# Mako_DSP_Power_R1_3.net
KiCad netlist of a schematic drawn in Altium Designer
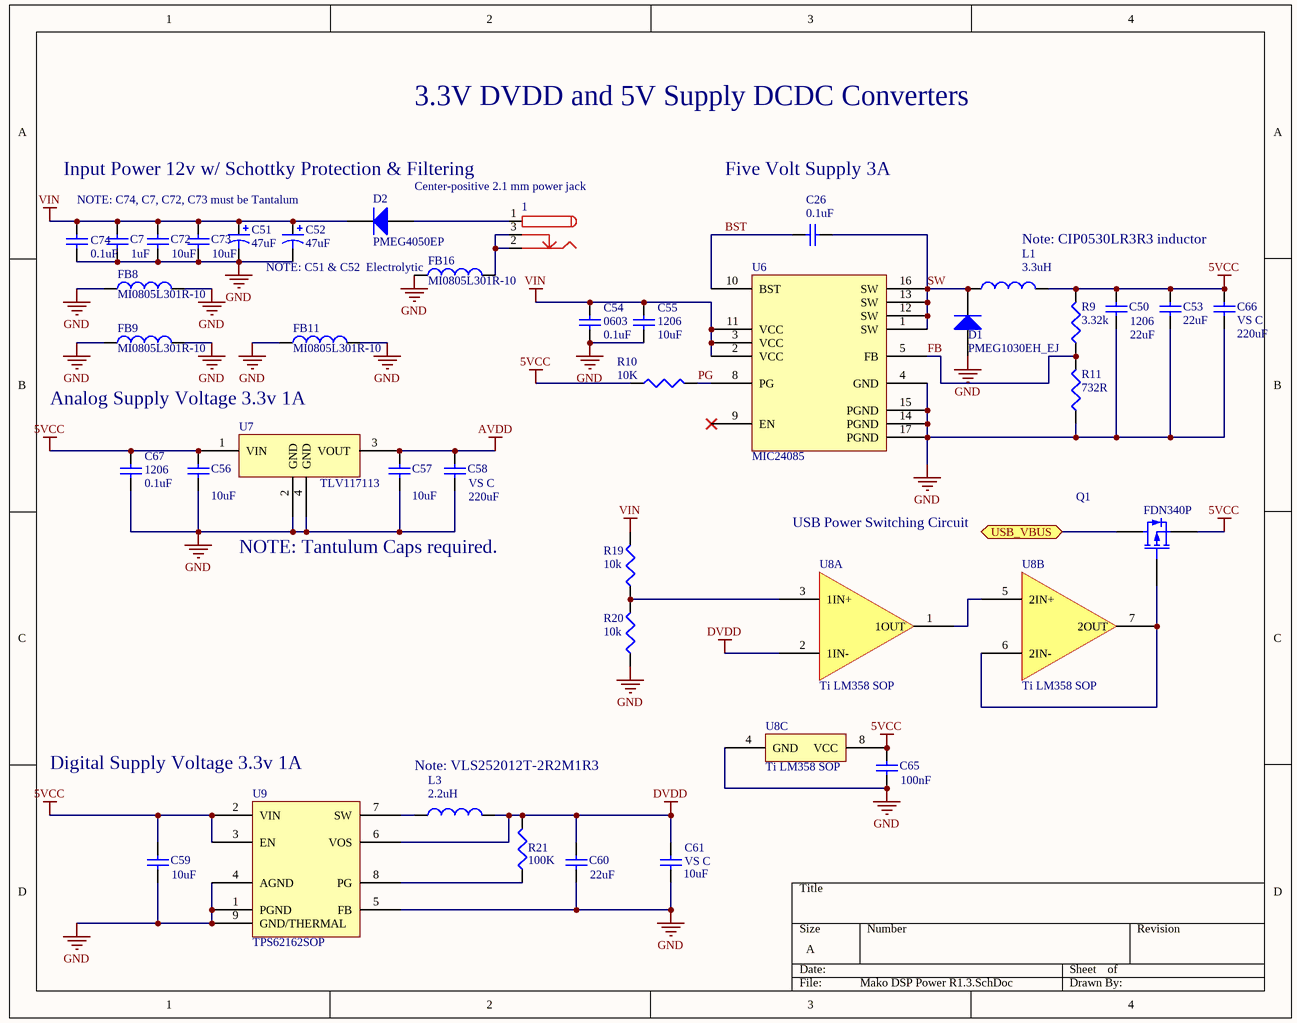
[diagram p0: Mako DSP Power R1.3.SchDoc]

(export (version "E")
  (design (tool "Eeschema 10.0.6"))
  (components
    (comp (ref "1")
      (value "Center-positive 2.1 mm power jack")
      (footprint "PJ-102AH")
      (description "Power jack")
      (fields (field (name "PUBLISHER") "Altium Limited"))
      (libsource (lib "Rascal") (part "PWR2.5"))
    )
    (comp (ref "C7")
      (value "1uF")
      (footprint "C1206")
      (description "Capacitor (Semiconductor SIM Model)")
      (fields (field (name "Comment") "Cap Semi") (field (name "PUBLISHER") "Altium Limited"))
      (libsource (lib "Miscellaneous Devices") (part "Cap Semi"))
    )
    (comp (ref "C26")
      (value "0.1uF")
      (footprint "1608[0603]")
      (description "Capacitor (Semiconductor SIM Model)")
      (fields (field (name "Comment") "Cap Semi") (field (name "PUBLISHER") "Altium Limited"))
      (libsource (lib "Miscellaneous Devices") (part "Cap Semi"))
    )
    (comp (ref "C50")
      (value "1206")
      (footprint "C1206")
      (description "Capacitor (Semiconductor SIM Model)")
      (fields (field (name "ALTIUM_VALUE") "22uF") (field (name "PUBLISHER") "Altium Limited"))
      (libsource (lib "Miscellaneous Devices") (part "Cap Semi"))
    )
    (comp (ref "C51")
      (value "47uF")
      (footprint "CAPPR2.5-6.3x5")
      (description "Polarized Capacitor (Radial)")
      (fields (field (name "Comment") "Cap Pol1") (field (name "PUBLISHER") "Altium Limited"))
      (libsource (lib "Miscellaneous Devices") (part "Cap Pol1"))
    )
    (comp (ref "C52")
      (value "47uF")
      (footprint "CAPPR2.5-6.3x5")
      (description "Polarized Capacitor (Radial)")
      (fields (field (name "Comment") "Cap Pol1") (field (name "PUBLISHER") "Altium Limited"))
      (libsource (lib "Miscellaneous Devices") (part "Cap Pol1"))
    )
    (comp (ref "C53")
      (value "22uF")
      (footprint "C1206")
      (description "Capacitor (Semiconductor SIM Model)")
      (fields (field (name "Comment") "Cap Semi") (field (name "PUBLISHER") "Altium Limited"))
      (libsource (lib "Miscellaneous Devices") (part "Cap Semi"))
    )
    (comp (ref "C54")
      (value "0603")
      (footprint "1608[0603]")
      (description "Capacitor (Semiconductor SIM Model)")
      (fields (field (name "ALTIUM_VALUE") "0.1uF") (field (name "PUBLISHER") "Altium Limited"))
      (libsource (lib "Miscellaneous Devices") (part "Cap Semi"))
    )
    (comp (ref "C55")
      (value "1206")
      (footprint "C1206")
      (description "Capacitor (Semiconductor SIM Model)")
      (fields (field (name "ALTIUM_VALUE") "10uF") (field (name "PUBLISHER") "Altium Limited"))
      (libsource (lib "Miscellaneous Devices") (part "Cap Semi"))
    )
    (comp (ref "C56")
      (value "10uF")
      (footprint "C1206")
      (description "Capacitor (Semiconductor SIM Model)")
      (fields (field (name "Comment") "Cap Semi") (field (name "PUBLISHER") "Altium Limited"))
      (libsource (lib "Miscellaneous Devices") (part "Cap Semi"))
    )
    (comp (ref "C57")
      (value "10uF")
      (footprint "C1206")
      (description "Capacitor (Semiconductor SIM Model)")
      (fields (field (name "Comment") "Cap Semi") (field (name "PUBLISHER") "Altium Limited"))
      (libsource (lib "Miscellaneous Devices") (part "Cap Semi"))
    )
    (comp (ref "C58")
      (value "VS C")
      (footprint "Panasonic VS C")
      (description "Capacitor (Semiconductor SIM Model)")
      (fields (field (name "ALTIUM_VALUE") "220uF") (field (name "PUBLISHER") "Altium Limited"))
      (libsource (lib "Miscellaneous Devices") (part "Cap Semi"))
    )
    (comp (ref "C59")
      (value "10uF")
      (footprint "C1206")
      (description "Capacitor (Semiconductor SIM Model)")
      (fields (field (name "Comment") "Cap Semi") (field (name "PUBLISHER") "Altium Limited"))
      (libsource (lib "Miscellaneous Devices") (part "Cap Semi"))
    )
    (comp (ref "C60")
      (value "22uF")
      (footprint "C1206")
      (description "Capacitor (Semiconductor SIM Model)")
      (fields (field (name "Comment") "Cap Semi") (field (name "PUBLISHER") "Altium Limited"))
      (libsource (lib "Miscellaneous Devices") (part "Cap Semi"))
    )
    (comp (ref "C61")
      (value "VS C")
      (footprint "Panasonic VS C")
      (description "Capacitor (Semiconductor SIM Model)")
      (fields (field (name "ALTIUM_VALUE") "10uF") (field (name "PUBLISHER") "Altium Limited"))
      (libsource (lib "Miscellaneous Devices") (part "Cap Semi"))
    )
    (comp (ref "C65")
      (value "100nF")
      (footprint "1608[0603]")
      (description "Capacitor (Semiconductor SIM Model)")
      (fields (field (name "Comment") "Cap Semi") (field (name "PUBLISHER") "Altium Limited"))
      (libsource (lib "Miscellaneous Devices") (part "Cap Semi"))
    )
    (comp (ref "C66")
      (value "VS C")
      (footprint "Panasonic VS C")
      (description "Capacitor (Semiconductor SIM Model)")
      (fields (field (name "ALTIUM_VALUE") "220uF") (field (name "PUBLISHER") "Altium Limited"))
      (libsource (lib "Miscellaneous Devices") (part "Cap Semi"))
    )
    (comp (ref "C67")
      (value "1206")
      (footprint "C1206")
      (description "Capacitor (Semiconductor SIM Model)")
      (fields (field (name "ALTIUM_VALUE") "0.1uF") (field (name "PUBLISHER") "Altium Limited"))
      (libsource (lib "Miscellaneous Devices") (part "Cap Semi"))
    )
    (comp (ref "C72")
      (value "10uF")
      (footprint "C1206")
      (description "Capacitor (Semiconductor SIM Model)")
      (fields (field (name "Comment") "Cap Semi") (field (name "PUBLISHER") "Altium Limited"))
      (libsource (lib "Miscellaneous Devices") (part "Cap Semi"))
    )
    (comp (ref "C73")
      (value "10uF")
      (footprint "C1206")
      (description "Capacitor (Semiconductor SIM Model)")
      (fields (field (name "Comment") "Cap Semi") (field (name "PUBLISHER") "Altium Limited"))
      (libsource (lib "Miscellaneous Devices") (part "Cap Semi"))
    )
    (comp (ref "C74")
      (value "0.1uF")
      (footprint "C1206")
      (description "Capacitor (Semiconductor SIM Model)")
      (fields (field (name "Comment") "Cap Semi") (field (name "PUBLISHER") "Altium Limited"))
      (libsource (lib "Miscellaneous Devices") (part "Cap Semi"))
    )
    (comp (ref "D1")
      (value "PMEG1030EH_EJ")
      (footprint "PMEG1030EH_EJ")
      (description "Default Diode")
      (fields (field (name "PUBLISHER") "Altium Limited"))
      (libsource (lib "") (part "Diode_1"))
    )
    (comp (ref "D2")
      (value "PMEG4050EP")
      (footprint "PMEG4050EP")
      (description "Default Diode")
      (fields (field (name "PUBLISHER") "Altium Limited"))
      (libsource (lib "Miscellaneous Devices") (part "Diode"))
    )
    (comp (ref "FB8")
      (value "MI0805L301R-10")
      (footprint "SM 0805 - gap trimmed")
      (description "Inductor")
      (fields (field (name "PUBLISHER") "Altium Limited"))
      (libsource (lib "Miscellaneous Devices") (part "Inductor"))
    )
    (comp (ref "FB9")
      (value "MI0805L301R-10")
      (footprint "SM 0805 - gap trimmed")
      (description "Inductor")
      (fields (field (name "PUBLISHER") "Altium Limited"))
      (libsource (lib "Miscellaneous Devices") (part "Inductor"))
    )
    (comp (ref "FB11")
      (value "MI0805L301R-10")
      (footprint "SM 0805 - gap trimmed")
      (description "Inductor")
      (fields (field (name "PUBLISHER") "Altium Limited"))
      (libsource (lib "Miscellaneous Devices") (part "Inductor"))
    )
    (comp (ref "FB16")
      (value "MI0805L301R-10")
      (footprint "SM 0805 - gap trimmed")
      (description "Inductor")
      (fields (field (name "PUBLISHER") "Altium Limited"))
      (libsource (lib "Miscellaneous Devices") (part "Inductor"))
    )
    (comp (ref "L1")
      (value "3.3uH")
      (footprint "CIP0530LR3R3")
      (description "Inductor")
      (fields (field (name "PUBLISHER") "Altium Limited"))
      (libsource (lib "Miscellaneous Devices") (part "Inductor"))
    )
    (comp (ref "L3")
      (value "2.2uH")
      (footprint "VLS252012T-2R2M1R3")
      (description "Inductor")
      (fields (field (name "PUBLISHER") "Altium Limited"))
      (libsource (lib "Miscellaneous Devices") (part "Inductor"))
    )
    (comp (ref "Q1")
      (value "FDN340P")
      (footprint "SOT23-3N")
      (description "P-Channel MOSFET")
      (fields (field (name "PUBLISHER") "Altium Limited"))
      (libsource (lib "Mako DSP Schematic Library") (part "FDN340P"))
    )
    (comp (ref "R9")
      (value "3.32k")
      (footprint "J1-0603")
      (description "Resistor")
      (fields (field (name "Comment") "Res3") (field (name "PUBLISHER") "Altium Limited"))
      (libsource (lib "Miscellaneous Devices") (part "Res3"))
    )
    (comp (ref "R10")
      (value "10K")
      (footprint "J1-0603")
      (description "Resistor")
      (fields (field (name "Comment") "Res3") (field (name "PUBLISHER") "Altium Limited"))
      (libsource (lib "Miscellaneous Devices") (part "Res3"))
    )
    (comp (ref "R11")
      (value "732R")
      (footprint "J1-0603")
      (description "Resistor")
      (fields (field (name "Comment") "Res3") (field (name "PUBLISHER") "Altium Limited"))
      (libsource (lib "Miscellaneous Devices") (part "Res3"))
    )
    (comp (ref "R19")
      (value "10k")
      (footprint "J1-0603")
      (description "Resistor")
      (fields (field (name "Comment") "Res3") (field (name "PUBLISHER") "Altium Limited"))
      (libsource (lib "Miscellaneous Devices") (part "Res3"))
    )
    (comp (ref "R20")
      (value "10k")
      (footprint "J1-0603")
      (description "Resistor")
      (fields (field (name "Comment") "Res3") (field (name "PUBLISHER") "Altium Limited"))
      (libsource (lib "Miscellaneous Devices") (part "Res3"))
    )
    (comp (ref "R21")
      (value "100K")
      (footprint "RESC2012L")
      (description "Resistor")
      (fields (field (name "Comment") "Res3") (field (name "PUBLISHER") "Altium Limited"))
      (libsource (lib "Miscellaneous Devices") (part "Res3"))
    )
    (comp (ref "U6")
      (value "MIC24085")
      (footprint "MIC24085-AYML")
      (libsource (lib "Adams Altium Library") (part "MIC24085"))
    )
    (comp (ref "U7")
      (value "TLV117113")
      (footprint "TLV117112")
      (description "Linear Regulator")
      (libsource (lib "Adams Altium Library") (part "TLV117112"))
    )
    (comp (ref "U8")
      (value "Ti LM358 SOP")
      (footprint "LM358")
      (libsource (lib "Mako DSP Schematic Library") (part "LM358_Symbol"))
    )
    (comp (ref "U9")
      (value "TPS62162SOP")
      (footprint "TPS62162SOP")
      (libsource (lib "Adams Altium Library") (part "TPS62162SOP"))
    )
  )
  (nets
    (net (code "1") (name "/BST") (class "Default")
      (node (ref "C26") (pin "2") (pinfunction "2_2") (pintype "passive"))
      (node (ref "U6") (pin "10") (pinfunction "BST_10") (pintype "passive"))
    )
    (net (code "2") (name "/FB") (class "Default")
      (node (ref "R11") (pin "2") (pinfunction "2_2") (pintype "passive"))
      (node (ref "R9") (pin "1") (pinfunction "1_1") (pintype "passive"))
      (node (ref "U6") (pin "5") (pinfunction "FB_5") (pintype "passive"))
    )
    (net (code "3") (name "/PG") (class "Default")
      (node (ref "R10") (pin "2") (pinfunction "2_2") (pintype "passive"))
      (node (ref "U6") (pin "8") (pinfunction "PG_8") (pintype "passive"))
    )
    (net (code "4") (name "/SW") (class "Default")
      (node (ref "C26") (pin "1") (pinfunction "1_1") (pintype "passive"))
      (node (ref "D1") (pin "2") (pinfunction "K_2") (pintype "passive"))
      (node (ref "L1") (pin "1") (pinfunction "1_1") (pintype "passive"))
      (node (ref "U6") (pin "1") (pinfunction "SW_1") (pintype "passive"))
      (node (ref "U6") (pin "12") (pinfunction "SW_12") (pintype "passive"))
      (node (ref "U6") (pin "13") (pinfunction "SW_13") (pintype "passive"))
      (node (ref "U6") (pin "16") (pinfunction "SW_16") (pintype "passive"))
    )
    (net (code "5") (name "/USB_VBUS") (class "Default")
      (node (ref "Q1") (pin "3") (pinfunction "S_3") (pintype "passive"))
    )
    (net (code "6") (name "5VCC") (class "Default")
      (node (ref "C50") (pin "2") (pinfunction "2_2") (pintype "passive"))
      (node (ref "C53") (pin "1") (pinfunction "1_1") (pintype "passive"))
      (node (ref "C56") (pin "1") (pinfunction "1_1") (pintype "passive"))
      (node (ref "C59") (pin "2") (pinfunction "2_2") (pintype "passive"))
      (node (ref "C65") (pin "1") (pinfunction "1_1") (pintype "passive"))
      (node (ref "C66") (pin "2") (pinfunction "2_2") (pintype "passive"))
      (node (ref "C67") (pin "2") (pinfunction "2_2") (pintype "passive"))
      (node (ref "L1") (pin "2") (pinfunction "2_2") (pintype "passive"))
      (node (ref "Q1") (pin "2") (pinfunction "D_2") (pintype "passive"))
      (node (ref "R10") (pin "1") (pinfunction "1_1") (pintype "passive"))
      (node (ref "R9") (pin "2") (pinfunction "2_2") (pintype "passive"))
      (node (ref "U7") (pin "1") (pinfunction "VIN_1") (pintype "passive"))
      (node (ref "U8") (pin "8") (pinfunction "VCC_8") (pintype "passive"))
      (node (ref "U9") (pin "2") (pinfunction "VIN_2") (pintype "passive"))
      (node (ref "U9") (pin "3") (pinfunction "EN_3") (pintype "passive"))
    )
    (net (code "7") (name "AVDD") (class "Default")
      (node (ref "C57") (pin "1") (pinfunction "1_1") (pintype "passive"))
      (node (ref "C58") (pin "1") (pinfunction "1_1") (pintype "passive"))
      (node (ref "U7") (pin "3") (pinfunction "VOUT_3") (pintype "passive"))
    )
    (net (code "8") (name "DVDD") (class "Default")
      (node (ref "C60") (pin "2") (pinfunction "2_2") (pintype "passive"))
      (node (ref "C61") (pin "1") (pinfunction "1_1") (pintype "passive"))
      (node (ref "L3") (pin "2") (pinfunction "2_2") (pintype "passive"))
      (node (ref "R21") (pin "2") (pinfunction "2_2") (pintype "passive"))
      (node (ref "U8") (pin "2") (pinfunction "1IN-_2") (pintype "passive"))
      (node (ref "U9") (pin "6") (pinfunction "VOS_6") (pintype "passive"))
    )
    (net (code "9") (name "GND") (class "Default")
      (node (ref "C50") (pin "1") (pinfunction "1_1") (pintype "passive"))
      (node (ref "C51") (pin "2") (pinfunction "2_2") (pintype "passive"))
      (node (ref "C52") (pin "2") (pinfunction "2_2") (pintype "passive"))
      (node (ref "C53") (pin "2") (pinfunction "2_2") (pintype "passive"))
      (node (ref "C54") (pin "1") (pinfunction "1_1") (pintype "passive"))
      (node (ref "C55") (pin "1") (pinfunction "1_1") (pintype "passive"))
      (node (ref "C56") (pin "2") (pinfunction "2_2") (pintype "passive"))
      (node (ref "C57") (pin "2") (pinfunction "2_2") (pintype "passive"))
      (node (ref "C58") (pin "2") (pinfunction "2_2") (pintype "passive"))
      (node (ref "C59") (pin "1") (pinfunction "1_1") (pintype "passive"))
      (node (ref "C60") (pin "1") (pinfunction "1_1") (pintype "passive"))
      (node (ref "C61") (pin "2") (pinfunction "2_2") (pintype "passive"))
      (node (ref "C65") (pin "2") (pinfunction "2_2") (pintype "passive"))
      (node (ref "C66") (pin "1") (pinfunction "1_1") (pintype "passive"))
      (node (ref "C67") (pin "1") (pinfunction "1_1") (pintype "passive"))
      (node (ref "C7") (pin "1") (pinfunction "1_1") (pintype "passive"))
      (node (ref "C72") (pin "1") (pinfunction "1_1") (pintype "passive"))
      (node (ref "C73") (pin "1") (pinfunction "1_1") (pintype "passive"))
      (node (ref "C74") (pin "1") (pinfunction "1_1") (pintype "passive"))
      (node (ref "D1") (pin "1") (pinfunction "A_1") (pintype "passive"))
      (node (ref "FB11") (pin "1") (pinfunction "1_1") (pintype "passive"))
      (node (ref "FB11") (pin "2") (pinfunction "2_2") (pintype "passive"))
      (node (ref "FB16") (pin "1") (pinfunction "1_1") (pintype "passive"))
      (node (ref "FB8") (pin "1") (pinfunction "1_1") (pintype "passive"))
      (node (ref "FB8") (pin "2") (pinfunction "2_2") (pintype "passive"))
      (node (ref "FB9") (pin "1") (pinfunction "1_1") (pintype "passive"))
      (node (ref "FB9") (pin "2") (pinfunction "2_2") (pintype "passive"))
      (node (ref "R11") (pin "1") (pinfunction "1_1") (pintype "passive"))
      (node (ref "R20") (pin "1") (pinfunction "1_1") (pintype "passive"))
      (node (ref "U6") (pin "14") (pinfunction "PGND_14") (pintype "passive"))
      (node (ref "U6") (pin "15") (pinfunction "PGND_15") (pintype "passive"))
      (node (ref "U6") (pin "17") (pinfunction "PGND_17") (pintype "passive"))
      (node (ref "U6") (pin "4") (pinfunction "GND_4") (pintype "passive"))
      (node (ref "U7") (pin "2") (pinfunction "GND_2") (pintype "passive"))
      (node (ref "U7") (pin "4") (pinfunction "GND_4") (pintype "passive"))
      (node (ref "U8") (pin "4") (pinfunction "GND_4") (pintype "passive"))
      (node (ref "U9") (pin "1") (pinfunction "PGND_1") (pintype "passive"))
      (node (ref "U9") (pin "4") (pinfunction "AGND_4") (pintype "passive"))
      (node (ref "U9") (pin "5") (pinfunction "FB_5") (pintype "passive"))
      (node (ref "U9") (pin "9") (pinfunction "GND/THERMAL_9") (pintype "passive"))
    )
    (net (code "10") (name "Net-(1-Pad2)") (class "Default")
      (node (ref "1") (pin "2") (pinfunction "2_2") (pintype "power_in"))
      (node (ref "1") (pin "3") (pinfunction "3_3") (pintype "power_in"))
      (node (ref "FB16") (pin "2") (pinfunction "2_2") (pintype "passive"))
    )
    (net (code "11") (name "Net-(D2-K)") (class "Default")
      (node (ref "1") (pin "1") (pinfunction "1_1") (pintype "power_in"))
      (node (ref "D2") (pin "2") (pinfunction "K_2") (pintype "passive"))
    )
    (net (code "12") (name "Net-(Q1-G)") (class "Default")
      (node (ref "Q1") (pin "1") (pinfunction "G_1") (pintype "passive"))
      (node (ref "U8") (pin "6") (pinfunction "2IN-_6") (pintype "passive"))
      (node (ref "U8") (pin "7") (pinfunction "2OUT_7") (pintype "passive"))
    )
    (net (code "13") (name "Net-(U8A-1IN+)") (class "Default")
      (node (ref "R19") (pin "1") (pinfunction "1_1") (pintype "passive"))
      (node (ref "R20") (pin "2") (pinfunction "2_2") (pintype "passive"))
      (node (ref "U8") (pin "3") (pinfunction "1IN+_3") (pintype "passive"))
    )
    (net (code "14") (name "Net-(U8A-1OUT)") (class "Default")
      (node (ref "U8") (pin "1") (pinfunction "1OUT_1") (pintype "passive"))
      (node (ref "U8") (pin "5") (pinfunction "2IN+_5") (pintype "passive"))
    )
    (net (code "15") (name "Net-(U9-PG)") (class "Default")
      (node (ref "R21") (pin "1") (pinfunction "1_1") (pintype "passive"))
      (node (ref "U9") (pin "8") (pinfunction "PG_8") (pintype "passive"))
    )
    (net (code "16") (name "Net-(U9-SW)") (class "Default")
      (node (ref "L3") (pin "1") (pinfunction "1_1") (pintype "passive"))
      (node (ref "U9") (pin "7") (pinfunction "SW_7") (pintype "passive"))
    )
    (net (code "17") (name "VIN") (class "Default")
      (node (ref "C51") (pin "1") (pinfunction "1_1") (pintype "passive"))
      (node (ref "C52") (pin "1") (pinfunction "1_1") (pintype "passive"))
      (node (ref "C54") (pin "2") (pinfunction "2_2") (pintype "passive"))
      (node (ref "C55") (pin "2") (pinfunction "2_2") (pintype "passive"))
      (node (ref "C7") (pin "2") (pinfunction "2_2") (pintype "passive"))
      (node (ref "C72") (pin "2") (pinfunction "2_2") (pintype "passive"))
      (node (ref "C73") (pin "2") (pinfunction "2_2") (pintype "passive"))
      (node (ref "C74") (pin "2") (pinfunction "2_2") (pintype "passive"))
      (node (ref "D2") (pin "1") (pinfunction "A_1") (pintype "passive"))
      (node (ref "R19") (pin "2") (pinfunction "2_2") (pintype "passive"))
      (node (ref "U6") (pin "11") (pinfunction "VCC_11") (pintype "passive"))
      (node (ref "U6") (pin "2") (pinfunction "VCC_2") (pintype "passive"))
      (node (ref "U6") (pin "3") (pinfunction "VCC_3") (pintype "passive"))
    )
    (net (code "18") (name "unconnected-(U6-EN-Pad9)") (class "Default")
      (node (ref "U6") (pin "9") (pinfunction "EN_9") (pintype "passive+no_connect"))
    )
    (net (code "19") (name "unconnected-(U6-NC-Pad6)") (class "Default")
      (node (ref "U6") (pin "6") (pinfunction "NC_6") (pintype "passive"))
    )
    (net (code "20") (name "unconnected-(U6-NC-Pad7)") (class "Default")
      (node (ref "U6") (pin "7") (pinfunction "NC_7") (pintype "passive"))
    )
  )
)
